# Power_Vref.net
KiCad netlist of a schematic drawn in Altium Designer
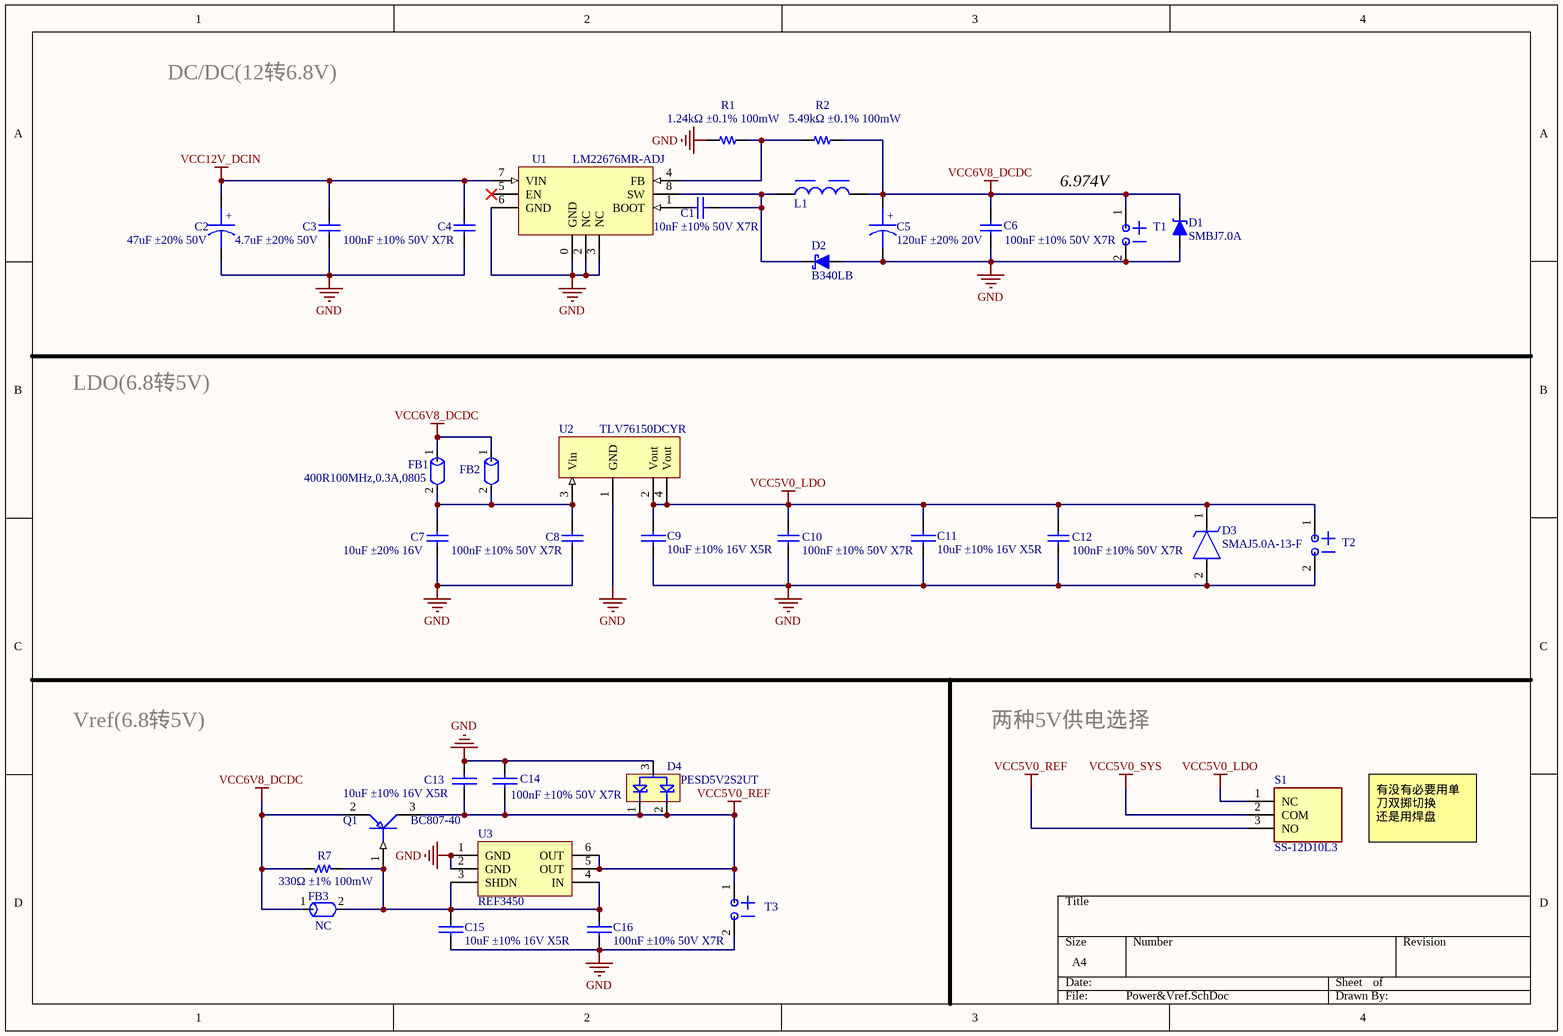
[diagram p0: Power&Vref.SchDoc]

(export (version "E")
  (design (tool "Eeschema 10.0.6"))
  (components
    (comp (ref "C1")
      (value "10nF ±10% 50V X7R")
      (footprint "C-0603")
      (description "贴片瓷介电容10nF±10%,0805")
      (libsource (lib "电容") (part "10nF_1"))
    )
    (comp (ref "C2")
      (value "47uF ±20% 50V")
      (footprint "CAP-SMD-φ6.3")
      (description "EEEFT1H470AP")
      (libsource (lib "电容") (part "10uF/16V贴片铝电解"))
    )
    (comp (ref "C3") (value "4.7uF ±20% 50V") (footprint "C-0805") (libsource (lib "Device") (part "C-1210")))
    (comp (ref "C4")
      (value "100nF ±10% 50V X7R")
      (footprint "C-0603")
      (libsource (lib "电容") (part "100nF_1"))
    )
    (comp (ref "C5")
      (value "120uF ±20% 20V")
      (footprint "CAP-SMD-φ6.3")
      (libsource (lib "电容") (part "100uF/25V贴片铝电解"))
    )
    (comp (ref "C6")
      (value "100nF ±10% 50V X7R")
      (footprint "C-0603")
      (libsource (lib "电容") (part "100nF_1"))
    )
    (comp (ref "C7") (value "10uF ±20% 16V") (footprint "C-0805") (libsource (lib "Device") (part "C-1210")))
    (comp (ref "C8")
      (value "100nF ±10% 50V X7R")
      (footprint "C-0603")
      (libsource (lib "电容") (part "100nF_1"))
    )
    (comp (ref "C9")
      (value "10uF ±10% 16V X5R")
      (footprint "C-0805")
      (description "Capacitor")
      (libsource (lib "*") (part "CAP"))
    )
    (comp (ref "C10")
      (value "100nF ±10% 50V X7R")
      (footprint "C-0603")
      (libsource (lib "电容") (part "100nF_1"))
    )
    (comp (ref "C11")
      (value "10uF ±10% 16V X5R")
      (footprint "C-0805")
      (description "Capacitor")
      (libsource (lib "*") (part "CAP"))
    )
    (comp (ref "C12")
      (value "100nF ±10% 50V X7R")
      (footprint "C-0603")
      (libsource (lib "电容") (part "100nF_1"))
    )
    (comp (ref "C13")
      (value "10uF ±10% 16V X5R")
      (footprint "C-0805")
      (description "Capacitor")
      (libsource (lib "*") (part "CAP"))
    )
    (comp (ref "C14") (value "100nF ±10% 50V X7R") (footprint "C-0603") (libsource (lib "") (part "CAP_1")))
    (comp (ref "C15")
      (value "10uF ±10% 16V X5R")
      (footprint "C-0805")
      (description "Capacitor")
      (libsource (lib "*") (part "CAP"))
    )
    (comp (ref "C16") (value "100nF ±10% 50V X7R") (footprint "C-0603") (libsource (lib "") (part "CAP_1")))
    (comp (ref "D1")
      (value "SMBJ7.0A")
      (footprint "DO-214AA/SMB")
      (libsource (lib "Device") (part "Diode-稳压-213AB/LL34/MiniMELF"))
    )
    (comp (ref "D2")
      (value "B340LB")
      (footprint "DO-214AA/SMB")
      (libsource (lib "Device") (part "Diode-肖特基-214AA  (SMB)"))
    )
    (comp (ref "D3")
      (value "SMAJ5.0A-13-F")
      (footprint "SamacSys:DIOM5226X230N")
      (description "TVS Diode (Uni-directional)")
      (fields (field (name "MOUSER PART NUMBER") "621-SMAJ5.0A-13-F"))
      (libsource (lib "*") (part "SMAJ5.0A-13-F"))
    )
    (comp (ref "D4") (value "PESD5V2S2UT") (footprint "sot23-3") (libsource (lib "IC") (part "PESDxS2UT")))
    (comp (ref "FB1")
      (value "400R100MHz,0.3A,0805")
      (footprint "R-0805")
      (description "Rdc0.3Ω,伍尔特,742792032")
      (libsource (lib "其它") (part "FB_1K/500mA_0805"))
    )
    (comp (ref "FB2")
      (value "400R100MHz,0.3A,0805")
      (footprint "R-0805")
      (description "Rdc0.3Ω,伍尔特,742792032")
      (libsource (lib "其它") (part "FB_1K/500mA_0805"))
    )
    (comp (ref "FB3")
      (value "NC")
      (footprint "R-0805")
      (description "Rdc0.3Ω,伍尔特,742792032")
      (libsource (lib "其它") (part "FB_1K/500mA_0805"))
    )
    (comp (ref "L1")
      (value "16µH, 6.25A")
      (footprint "WE-HCI_1050")
      (description "WE-HCI SMT Flat Wire High Current Inductor, size 1050, 16µH, 6.25A, 34.5mΩ")
      (fields
        (field (name "MANUFACTURER PART NUMBER") "7443251600")
        (field (name "MANUFACTURER") "Wurth Elektronik")
      )
      (libsource (lib "WE-HCI (rev22c)") (part "7443251600"))
    )
    (comp (ref "Q1") (value "BC807-40") (footprint "SOT23-3") (libsource (lib "NBP电源板封装") (part "BC807-40")))
    (comp (ref "R1")
      (value "1.24kΩ ±0.1% 100mW")
      (footprint "R-0603")
      (description "国巨RC0805FR-073K3")
      (libsource (lib "电阻") (part "3.3K_1"))
    )
    (comp (ref "R2")
      (value "5.49kΩ ±0.1% 100mW")
      (footprint "R-0603")
      (description "RT0603BRD075K49L")
      (libsource (lib "电阻") (part "10K_1"))
    )
    (comp (ref "R7")
      (value "330Ω ±1% 100mW")
      (footprint "R-0805")
      (description "国巨RC0805FR-07100R")
      (libsource (lib "电阻") (part "100Ω_1"))
    )
    (comp (ref "S1")
      (value "SS-12D10L3")
      (footprint "SamacSys:SS12D10L3")
      (description "Switch")
      (libsource (lib "*") (part "SS-12D10L3"))
    )
    (comp (ref "T1") (value "POWER_TEST") (footprint "BT") (libsource (lib "其它") (part "POWER_TEST")))
    (comp (ref "T2") (value "POWER_TEST") (footprint "BT") (libsource (lib "其它") (part "POWER_TEST")))
    (comp (ref "T3") (value "POWER_TEST") (footprint "BT") (libsource (lib "其它") (part "POWER_TEST")))
    (comp (ref "U1")
      (value "LM22676MR-ADJ")
      (footprint "SOIC-8(4.90*3.9)-EPAD")
      (libsource (lib "IC") (part "LM22676MR-ADJ"))
    )
    (comp (ref "U2")
      (value "TLV76150DCYR")
      (footprint "IC:SOT223")
      (description "品牌：TI，型号：LM1117IMP-3.3/NOPB，800-mA Low-Dropout，SOT223，-40~+ 125°C，ROHS")
      (libsource (lib "IC") (part "LM1117IMP-3.3/NOPB"))
    )
    (comp (ref "U3") (value "REF3450") (footprint "SOT23-6") (libsource (lib "*") (part "REF3225")))
  )
  (nets
    (net (code "1") (name "GND") (class "Default")
      (node (ref "C10") (pin "1") (pinfunction "1_1") (pintype "passive"))
      (node (ref "C11") (pin "1") (pinfunction "1_1") (pintype "passive"))
      (node (ref "C12") (pin "1") (pinfunction "1_1") (pintype "passive"))
      (node (ref "C13") (pin "1") (pinfunction "1_1") (pintype "passive"))
      (node (ref "C14") (pin "2") (pinfunction "2_2") (pintype "passive"))
      (node (ref "C15") (pin "1") (pinfunction "1_1") (pintype "passive"))
      (node (ref "C16") (pin "1") (pinfunction "1_1") (pintype "passive"))
      (node (ref "C2") (pin "2") (pinfunction "2_2") (pintype "passive"))
      (node (ref "C3") (pin "1") (pinfunction "1_1") (pintype "passive"))
      (node (ref "C4") (pin "1") (pinfunction "1_1") (pintype "passive"))
      (node (ref "C5") (pin "2") (pinfunction "2_2") (pintype "passive"))
      (node (ref "C6") (pin "1") (pinfunction "1_1") (pintype "passive"))
      (node (ref "C7") (pin "1") (pinfunction "1_1") (pintype "passive"))
      (node (ref "C8") (pin "1") (pinfunction "1_1") (pintype "passive"))
      (node (ref "C9") (pin "1") (pinfunction "1_1") (pintype "passive"))
      (node (ref "D1") (pin "A") (pinfunction "A_A") (pintype "passive"))
      (node (ref "D2") (pin "A") (pinfunction "A_A") (pintype "passive"))
      (node (ref "D3") (pin "2") (pinfunction "A_2") (pintype "passive"))
      (node (ref "D4") (pin "3") (pinfunction "3_3") (pintype "passive"))
      (node (ref "R1") (pin "1") (pinfunction "TOP_1") (pintype "passive"))
      (node (ref "T1") (pin "2") (pinfunction "-_2") (pintype "passive"))
      (node (ref "T2") (pin "2") (pinfunction "-_2") (pintype "passive"))
      (node (ref "T3") (pin "2") (pinfunction "-_2") (pintype "passive"))
      (node (ref "U1") (pin "0") (pinfunction "GND_0") (pintype "power_in"))
      (node (ref "U1") (pin "2") (pinfunction "NC_2") (pintype "passive"))
      (node (ref "U1") (pin "3") (pinfunction "NC_3") (pintype "passive"))
      (node (ref "U1") (pin "6") (pinfunction "GND_6") (pintype "power_in"))
      (node (ref "U2") (pin "1") (pinfunction "GND_1") (pintype "power_in"))
      (node (ref "U3") (pin "1") (pinfunction "GND_1") (pintype "passive"))
      (node (ref "U3") (pin "2") (pinfunction "GND_2") (pintype "passive"))
    )
    (net (code "2") (name "Net-(Q1-B)") (class "Default")
      (node (ref "C15") (pin "2") (pinfunction "2_2") (pintype "passive"))
      (node (ref "C16") (pin "2") (pinfunction "2_2") (pintype "passive"))
      (node (ref "FB3") (pin "2") (pinfunction "2_2") (pintype "passive"))
      (node (ref "Q1") (pin "1") (pinfunction "B_1") (pintype "input"))
      (node (ref "R7") (pin "1") (pinfunction "TOP_1") (pintype "passive"))
      (node (ref "U3") (pin "3") (pinfunction "SHDN_3") (pintype "passive"))
      (node (ref "U3") (pin "4") (pinfunction "IN_4") (pintype "passive"))
    )
    (net (code "3") (name "Net-(R1-BOT)") (class "Default")
      (node (ref "R1") (pin "2") (pinfunction "BOT_2") (pintype "passive"))
      (node (ref "R2") (pin "2") (pinfunction "BOT_2") (pintype "passive"))
      (node (ref "U1") (pin "4") (pinfunction "FB_4") (pintype "input"))
    )
    (net (code "4") (name "Net-(U1-BOOT)") (class "Default")
      (node (ref "C1") (pin "2") (pinfunction "2_2") (pintype "passive"))
      (node (ref "U1") (pin "1") (pinfunction "BOOT_1") (pintype "input"))
    )
    (net (code "5") (name "Net-(U1-SW)") (class "Default")
      (node (ref "C1") (pin "1") (pinfunction "1_1") (pintype "passive"))
      (node (ref "D2") (pin "K") (pinfunction "K_K") (pintype "passive"))
      (node (ref "L1") (pin "1") (pinfunction "1_1") (pintype "passive"))
      (node (ref "U1") (pin "8") (pinfunction "SW_8") (pintype "passive"))
    )
    (net (code "6") (name "Net-(U2-Vin)") (class "Default")
      (node (ref "C7") (pin "2") (pinfunction "2_2") (pintype "passive"))
      (node (ref "C8") (pin "2") (pinfunction "2_2") (pintype "passive"))
      (node (ref "FB1") (pin "2") (pinfunction "2_2") (pintype "passive"))
      (node (ref "FB2") (pin "2") (pinfunction "2_2") (pintype "passive"))
      (node (ref "U2") (pin "3") (pinfunction "Vin_3") (pintype "input"))
    )
    (net (code "7") (name "VCC5V0_LDO") (class "Default")
      (node (ref "C10") (pin "2") (pinfunction "2_2") (pintype "passive"))
      (node (ref "C11") (pin "2") (pinfunction "2_2") (pintype "passive"))
      (node (ref "C12") (pin "2") (pinfunction "2_2") (pintype "passive"))
      (node (ref "C9") (pin "2") (pinfunction "2_2") (pintype "passive"))
      (node (ref "D3") (pin "1") (pinfunction "K_1") (pintype "passive"))
      (node (ref "S1") (pin "1") (pinfunction "NC_1") (pintype "passive"))
      (node (ref "T2") (pin "1") (pinfunction "+_1") (pintype "passive"))
      (node (ref "U2") (pin "2") (pinfunction "Vout_2") (pintype "passive"))
      (node (ref "U2") (pin "4") (pinfunction "Vout_4") (pintype "passive"))
    )
    (net (code "8") (name "VCC5V0_REF") (class "Default")
      (node (ref "C13") (pin "2") (pinfunction "2_2") (pintype "passive"))
      (node (ref "C14") (pin "1") (pinfunction "1_1") (pintype "passive"))
      (node (ref "D4") (pin "1") (pinfunction "1_1") (pintype "passive"))
      (node (ref "D4") (pin "2") (pinfunction "2_2") (pintype "passive"))
      (node (ref "Q1") (pin "3") (pinfunction "C_3") (pintype "passive"))
      (node (ref "S1") (pin "3") (pinfunction "NO_3") (pintype "passive"))
      (node (ref "T3") (pin "1") (pinfunction "+_1") (pintype "passive"))
      (node (ref "U3") (pin "5") (pinfunction "OUT_5") (pintype "passive"))
      (node (ref "U3") (pin "6") (pinfunction "OUT_6") (pintype "passive"))
    )
    (net (code "9") (name "VCC5V0_SYS") (class "Default")
      (node (ref "S1") (pin "2") (pinfunction "COM_2") (pintype "passive"))
    )
    (net (code "10") (name "VCC6V8_DCDC") (class "Default")
      (node (ref "C5") (pin "1") (pinfunction "1_1") (pintype "passive"))
      (node (ref "C6") (pin "2") (pinfunction "2_2") (pintype "passive"))
      (node (ref "D1") (pin "K") (pinfunction "K_K") (pintype "passive"))
      (node (ref "FB1") (pin "1") (pinfunction "1_1") (pintype "passive"))
      (node (ref "FB2") (pin "1") (pinfunction "1_1") (pintype "passive"))
      (node (ref "FB3") (pin "1") (pinfunction "1_1") (pintype "passive"))
      (node (ref "L1") (pin "2") (pinfunction "2_2") (pintype "passive"))
      (node (ref "Q1") (pin "2") (pinfunction "E_2") (pintype "passive"))
      (node (ref "R2") (pin "1") (pinfunction "TOP_1") (pintype "passive"))
      (node (ref "R7") (pin "2") (pinfunction "BOT_2") (pintype "passive"))
      (node (ref "T1") (pin "1") (pinfunction "+_1") (pintype "passive"))
    )
    (net (code "11") (name "VCC12V_DCIN") (class "Default")
      (node (ref "C2") (pin "1") (pinfunction "1_1") (pintype "passive"))
      (node (ref "C3") (pin "2") (pinfunction "2_2") (pintype "passive"))
      (node (ref "C4") (pin "2") (pinfunction "2_2") (pintype "passive"))
      (node (ref "U1") (pin "7") (pinfunction "VIN_7") (pintype "input"))
    )
    (net (code "12") (name "unconnected-(U1-EN-Pad5)") (class "Default")
      (node (ref "U1") (pin "5") (pinfunction "EN_5") (pintype "passive+no_connect"))
    )
  )
)
